# DICO_giangrandi_flipped_v100.net
KiCad netlist of a schematic drawn in EAGLE
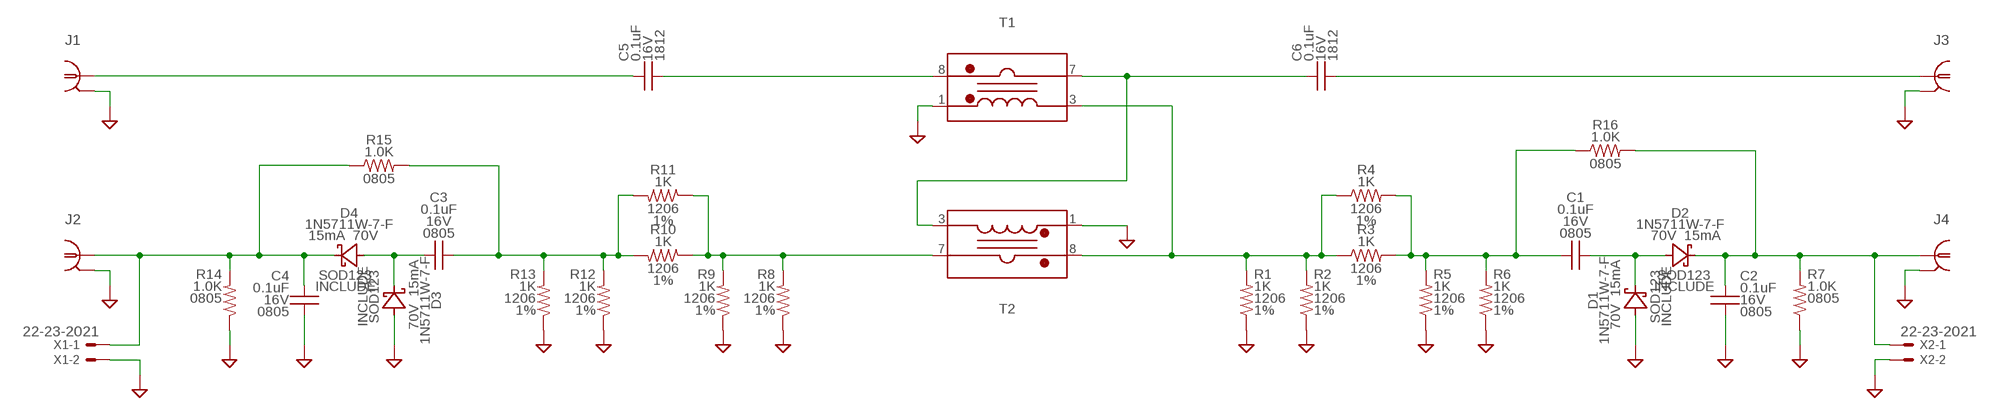
[diagram p0: schematic, sheet 1]

(export (version "E")
  (design (tool "Eeschema 10.0.6"))
  (components
    (comp (ref "C1")
      (value "0.1uF")
      (footprint "eagle-import:0805_IPC-7351B")
      (fields (field (name "PACKAGE") "0805") (field (name "VOLTAGE") "16V"))
      (libsource (lib "eagle-import") (part "C0805_IPCC-0.1U-16V-0805-X7R"))
    )
    (comp (ref "C2")
      (value "0.1uF")
      (footprint "eagle-import:0805_IPC-7351B")
      (fields (field (name "VOLTAGE") "16V"))
      (libsource (lib "eagle-import") (part "C0805_IPCC-0.1U-16V-0805-X7R"))
    )
    (comp (ref "C3")
      (value "0.1uF")
      (footprint "eagle-import:0805_IPC-7351B")
      (fields (field (name "PACKAGE") "0805") (field (name "VOLTAGE") "16V"))
      (libsource (lib "eagle-import") (part "C0805_IPCC-0.1U-16V-0805-X7R"))
    )
    (comp (ref "C4")
      (value "0.1uF")
      (footprint "eagle-import:0805_IPC-7351B")
      (fields (field (name "VOLTAGE") "16V"))
      (libsource (lib "eagle-import") (part "C0805_IPCC-0.1U-16V-0805-X7R"))
    )
    (comp (ref "C5")
      (value "0.1uF")
      (footprint "eagle-import:C1812")
      (fields (field (name "VOLTAGE") "16V"))
      (libsource (lib "eagle-import") (part "CC1812"))
    )
    (comp (ref "C6")
      (value "0.1uF")
      (footprint "eagle-import:C1812")
      (fields (field (name "VOLTAGE") "16V"))
      (libsource (lib "eagle-import") (part "CC1812"))
    )
    (comp (ref "D1")
      (value "D-SCHOTTKY1N5711W-7-FSOD123")
      (footprint "eagle-import:SOD123")
      (fields (field (name "PARTNO") "1N5711W-7-F") (field (name "VOLTAGE") "70V"))
      (libsource (lib "eagle-import") (part "D-SCHOTTKYSOD1231N5711W-7-F"))
    )
    (comp (ref "D2")
      (value "D-SCHOTTKY1N5711W-7-FSOD123")
      (footprint "eagle-import:SOD123")
      (fields (field (name "PARTNO") "1N5711W-7-F") (field (name "VOLTAGE") "70V"))
      (libsource (lib "eagle-import") (part "D-SCHOTTKYSOD1231N5711W-7-F"))
    )
    (comp (ref "D3")
      (value "D-SCHOTTKY1N5711W-7-FSOD123")
      (footprint "eagle-import:SOD123")
      (fields (field (name "PARTNO") "1N5711W-7-F") (field (name "VOLTAGE") "70V"))
      (libsource (lib "eagle-import") (part "D-SCHOTTKYSOD1231N5711W-7-F"))
    )
    (comp (ref "D4")
      (value "D-SCHOTTKY1N5711W-7-FSOD123")
      (footprint "eagle-import:SOD123")
      (fields (field (name "PARTNO") "1N5711W-7-F") (field (name "VOLTAGE") "70V"))
      (libsource (lib "eagle-import") (part "D-SCHOTTKYSOD1231N5711W-7-F"))
    )
    (comp (ref "J1")
      (value "COAXSMA_0.375WIDE")
      (footprint "eagle-import:SMA_EDGE_0.375WIDE")
      (libsource (lib "eagle-import") (part "COAXSMA_0.375WIDE"))
    )
    (comp (ref "J2")
      (value "COAXSMA_0.375WIDE")
      (footprint "eagle-import:SMA_EDGE_0.375WIDE")
      (libsource (lib "eagle-import") (part "COAXSMA_0.375WIDE"))
    )
    (comp (ref "J3")
      (value "COAXSMA_0.375WIDE")
      (footprint "eagle-import:SMA_EDGE_0.375WIDE")
      (libsource (lib "eagle-import") (part "COAXSMA_0.375WIDE"))
    )
    (comp (ref "J4")
      (value "COAXSMA_0.375WIDE")
      (footprint "eagle-import:SMA_EDGE_0.375WIDE")
      (libsource (lib "eagle-import") (part "COAXSMA_0.375WIDE"))
    )
    (comp (ref "R1")
      (value "1K")
      (footprint "eagle-import:1206_IPC-7351B")
      (fields (field (name "POWER") "0.25"))
      (libsource (lib "eagle-import") (part "R1206_IPCR-1.0K-1%-1206-0.25W"))
    )
    (comp (ref "R2")
      (value "1K")
      (footprint "eagle-import:1206_IPC-7351B")
      (fields (field (name "POWER") "0.25"))
      (libsource (lib "eagle-import") (part "R1206_IPCR-1.0K-1%-1206-0.25W"))
    )
    (comp (ref "R3")
      (value "1K")
      (footprint "eagle-import:1206_IPC-7351B")
      (fields (field (name "POWER") "0.25"))
      (libsource (lib "eagle-import") (part "R901206_IPCR-1.0K-1%-1206-0.25W"))
    )
    (comp (ref "R4")
      (value "1K")
      (footprint "eagle-import:1206_IPC-7351B")
      (fields (field (name "POWER") "0.25"))
      (libsource (lib "eagle-import") (part "R901206_IPCR-1.0K-1%-1206-0.25W"))
    )
    (comp (ref "R5")
      (value "1K")
      (footprint "eagle-import:1206_IPC-7351B")
      (fields (field (name "POWER") "0.25"))
      (libsource (lib "eagle-import") (part "R1206_IPCR-1.0K-1%-1206-0.25W"))
    )
    (comp (ref "R6")
      (value "1K")
      (footprint "eagle-import:1206_IPC-7351B")
      (fields (field (name "POWER") "0.25"))
      (libsource (lib "eagle-import") (part "R1206_IPCR-1.0K-1%-1206-0.25W"))
    )
    (comp (ref "R7")
      (value "1.0K")
      (footprint "eagle-import:0805_IPC-7351B")
      (libsource (lib "eagle-import") (part "R0805_IPCR-1.0K-0.1%-0805-0.1W"))
    )
    (comp (ref "R8")
      (value "1K")
      (footprint "eagle-import:1206_IPC-7351B")
      (fields (field (name "POWER") "0.25"))
      (libsource (lib "eagle-import") (part "R1206_IPCR-1.0K-1%-1206-0.25W"))
    )
    (comp (ref "R9")
      (value "1K")
      (footprint "eagle-import:1206_IPC-7351B")
      (fields (field (name "POWER") "0.25"))
      (libsource (lib "eagle-import") (part "R1206_IPCR-1.0K-1%-1206-0.25W"))
    )
    (comp (ref "R10")
      (value "1K")
      (footprint "eagle-import:1206_IPC-7351B")
      (fields (field (name "POWER") "0.25"))
      (libsource (lib "eagle-import") (part "R901206_IPCR-1.0K-1%-1206-0.25W"))
    )
    (comp (ref "R11")
      (value "1K")
      (footprint "eagle-import:1206_IPC-7351B")
      (fields (field (name "POWER") "0.25"))
      (libsource (lib "eagle-import") (part "R901206_IPCR-1.0K-1%-1206-0.25W"))
    )
    (comp (ref "R12")
      (value "1K")
      (footprint "eagle-import:1206_IPC-7351B")
      (fields (field (name "POWER") "0.25"))
      (libsource (lib "eagle-import") (part "R1206_IPCR-1.0K-1%-1206-0.25W"))
    )
    (comp (ref "R13")
      (value "1K")
      (footprint "eagle-import:1206_IPC-7351B")
      (fields (field (name "POWER") "0.25"))
      (libsource (lib "eagle-import") (part "R1206_IPCR-1.0K-1%-1206-0.25W"))
    )
    (comp (ref "R14")
      (value "1.0K")
      (footprint "eagle-import:0805_IPC-7351B")
      (libsource (lib "eagle-import") (part "R0805_IPCR-1.0K-0.1%-0805-0.1W"))
    )
    (comp (ref "R15")
      (value "1.0K")
      (footprint "eagle-import:0805_IPC-7351B")
      (libsource (lib "eagle-import") (part "R900805_IPCR-1.0K-0.1%-0805-0.1W"))
    )
    (comp (ref "R16")
      (value "1.0K")
      (footprint "eagle-import:0805_IPC-7351B")
      (libsource (lib "eagle-import") (part "R900805_IPCR-1.0K-0.1%-0805-0.1W"))
    )
    (comp (ref "T1")
      (value "TRAFO_CURRENTSENSEPA1005_NOCENTERPADS")
      (footprint "eagle-import:PA1005_NOCENTERPADS")
      (libsource (lib "eagle-import") (part "TRAFO_CURRENTSENSEPA1005_NOCENTERPADS"))
    )
    (comp (ref "T2")
      (value "TRAFO_CURRENTSENSEPA1005_NOCENTERPADS")
      (footprint "eagle-import:PA1005_NOCENTERPADS")
      (libsource (lib "eagle-import") (part "TRAFO_CURRENTSENSEPA1005_NOCENTERPADS"))
    )
    (comp (ref "X1")
      (value "22-23-2021")
      (footprint "eagle-import:22-23-2021")
      (fields (field (name "MF") "MOLEX"))
      (libsource (lib "eagle-import") (part "22-23-2021"))
    )
    (comp (ref "X2")
      (value "22-23-2021")
      (footprint "eagle-import:22-23-2021")
      (fields (field (name "MF") "MOLEX"))
      (libsource (lib "eagle-import") (part "22-23-2021"))
    )
  )
  (nets
    (net (code "1") (name "GND") (class "Default")
      (node (ref "C2") (pin "2") (pinfunction "2_2") (pintype "passive"))
      (node (ref "C4") (pin "2") (pinfunction "2_2") (pintype "passive"))
      (node (ref "D1") (pin "A") (pinfunction "A1_A") (pintype "passive"))
      (node (ref "D3") (pin "A") (pinfunction "A1_A") (pintype "passive"))
      (node (ref "J1") (pin "S1") (pinfunction "GND1_S1") (pintype "power_in"))
      (node (ref "J1") (pin "S2") (pinfunction "GND1_S2") (pintype "power_in"))
      (node (ref "J1") (pin "S3") (pinfunction "GND1_S3") (pintype "power_in"))
      (node (ref "J1") (pin "S4") (pinfunction "GND1_S4") (pintype "power_in"))
      (node (ref "J2") (pin "S1") (pinfunction "GND1_S1") (pintype "power_in"))
      (node (ref "J2") (pin "S2") (pinfunction "GND1_S2") (pintype "power_in"))
      (node (ref "J2") (pin "S3") (pinfunction "GND1_S3") (pintype "power_in"))
      (node (ref "J2") (pin "S4") (pinfunction "GND1_S4") (pintype "power_in"))
      (node (ref "J3") (pin "S1") (pinfunction "GND1_S1") (pintype "power_in"))
      (node (ref "J3") (pin "S2") (pinfunction "GND1_S2") (pintype "power_in"))
      (node (ref "J3") (pin "S3") (pinfunction "GND1_S3") (pintype "power_in"))
      (node (ref "J3") (pin "S4") (pinfunction "GND1_S4") (pintype "power_in"))
      (node (ref "J4") (pin "S1") (pinfunction "GND1_S1") (pintype "power_in"))
      (node (ref "J4") (pin "S2") (pinfunction "GND1_S2") (pintype "power_in"))
      (node (ref "J4") (pin "S3") (pinfunction "GND1_S3") (pintype "power_in"))
      (node (ref "J4") (pin "S4") (pinfunction "GND1_S4") (pintype "power_in"))
      (node (ref "R1") (pin "2") (pinfunction "2_2") (pintype "passive"))
      (node (ref "R12") (pin "2") (pinfunction "2_2") (pintype "passive"))
      (node (ref "R13") (pin "2") (pinfunction "2_2") (pintype "passive"))
      (node (ref "R14") (pin "2") (pinfunction "2_2") (pintype "passive"))
      (node (ref "R2") (pin "2") (pinfunction "2_2") (pintype "passive"))
      (node (ref "R5") (pin "2") (pinfunction "2_2") (pintype "passive"))
      (node (ref "R6") (pin "2") (pinfunction "2_2") (pintype "passive"))
      (node (ref "R7") (pin "2") (pinfunction "2_2") (pintype "passive"))
      (node (ref "R8") (pin "2") (pinfunction "2_2") (pintype "passive"))
      (node (ref "R9") (pin "2") (pinfunction "2_2") (pintype "passive"))
      (node (ref "T1") (pin "1") (pinfunction "SS_1") (pintype "passive"))
      (node (ref "T2") (pin "1") (pinfunction "SS_1") (pintype "passive"))
      (node (ref "X1") (pin "2") (pinfunction "S_2") (pintype "passive"))
      (node (ref "X2") (pin "2") (pinfunction "S_2") (pintype "passive"))
    )
    (net (code "2") (name "Net-(C1-Pad1)") (class "Default")
      (node (ref "C1") (pin "1") (pinfunction "1_1") (pintype "passive"))
      (node (ref "R16") (pin "1") (pinfunction "1_1") (pintype "passive"))
      (node (ref "R3") (pin "2") (pinfunction "2_2") (pintype "passive"))
      (node (ref "R4") (pin "2") (pinfunction "2_2") (pintype "passive"))
      (node (ref "R5") (pin "1") (pinfunction "1_1") (pintype "passive"))
      (node (ref "R6") (pin "1") (pinfunction "1_1") (pintype "passive"))
    )
    (net (code "3") (name "Net-(C3-Pad1)") (class "Default")
      (node (ref "C3") (pin "1") (pinfunction "1_1") (pintype "passive"))
      (node (ref "R10") (pin "2") (pinfunction "2_2") (pintype "passive"))
      (node (ref "R11") (pin "2") (pinfunction "2_2") (pintype "passive"))
      (node (ref "R12") (pin "1") (pinfunction "1_1") (pintype "passive"))
      (node (ref "R13") (pin "1") (pinfunction "1_1") (pintype "passive"))
      (node (ref "R15") (pin "2") (pinfunction "2_2") (pintype "passive"))
    )
    (net (code "4") (name "Net-(D1-C1)") (class "Default")
      (node (ref "C1") (pin "2") (pinfunction "2_2") (pintype "passive"))
      (node (ref "D1") (pin "K") (pinfunction "C1_K") (pintype "passive"))
      (node (ref "D2") (pin "A") (pinfunction "A1_A") (pintype "passive"))
    )
    (net (code "5") (name "Net-(D2-C1)") (class "Default")
      (node (ref "C2") (pin "1") (pinfunction "1_1") (pintype "passive"))
      (node (ref "D2") (pin "K") (pinfunction "C1_K") (pintype "passive"))
      (node (ref "J4") (pin "C") (pinfunction "1_C") (pintype "passive"))
      (node (ref "R16") (pin "2") (pinfunction "2_2") (pintype "passive"))
      (node (ref "R7") (pin "1") (pinfunction "1_1") (pintype "passive"))
      (node (ref "X2") (pin "1") (pinfunction "S_1") (pintype "passive"))
    )
    (net (code "6") (name "Net-(D3-C1)") (class "Default")
      (node (ref "C3") (pin "2") (pinfunction "2_2") (pintype "passive"))
      (node (ref "D3") (pin "K") (pinfunction "C1_K") (pintype "passive"))
      (node (ref "D4") (pin "A") (pinfunction "A1_A") (pintype "passive"))
    )
    (net (code "7") (name "Net-(D4-C1)") (class "Default")
      (node (ref "C4") (pin "1") (pinfunction "1_1") (pintype "passive"))
      (node (ref "D4") (pin "K") (pinfunction "C1_K") (pintype "passive"))
      (node (ref "J2") (pin "C") (pinfunction "1_C") (pintype "passive"))
      (node (ref "R14") (pin "1") (pinfunction "1_1") (pintype "passive"))
      (node (ref "R15") (pin "1") (pinfunction "1_1") (pintype "passive"))
      (node (ref "X1") (pin "1") (pinfunction "S_1") (pintype "passive"))
    )
    (net (code "8") (name "Net-(J1-1)") (class "Default")
      (node (ref "C5") (pin "1") (pinfunction "1_1") (pintype "passive"))
      (node (ref "J1") (pin "C") (pinfunction "1_C") (pintype "passive"))
    )
    (net (code "9") (name "Net-(J3-1)") (class "Default")
      (node (ref "C6") (pin "2") (pinfunction "2_2") (pintype "passive"))
      (node (ref "J3") (pin "C") (pinfunction "1_C") (pintype "passive"))
    )
    (net (code "10") (name "Net-(T1-PF)") (class "Default")
      (node (ref "C6") (pin "1") (pinfunction "1_1") (pintype "passive"))
      (node (ref "T1") (pin "7") (pinfunction "PF_7") (pintype "passive"))
      (node (ref "T2") (pin "3") (pinfunction "SF_3") (pintype "passive"))
    )
    (net (code "11") (name "Net-(T1-PS)") (class "Default")
      (node (ref "C5") (pin "2") (pinfunction "2_2") (pintype "passive"))
      (node (ref "T1") (pin "8") (pinfunction "PS_8") (pintype "passive"))
    )
    (net (code "12") (name "Net-(T1-SF)") (class "Default")
      (node (ref "R1") (pin "1") (pinfunction "1_1") (pintype "passive"))
      (node (ref "R2") (pin "1") (pinfunction "1_1") (pintype "passive"))
      (node (ref "R3") (pin "1") (pinfunction "1_1") (pintype "passive"))
      (node (ref "R4") (pin "1") (pinfunction "1_1") (pintype "passive"))
      (node (ref "T1") (pin "3") (pinfunction "SF_3") (pintype "passive"))
      (node (ref "T2") (pin "8") (pinfunction "PS_8") (pintype "passive"))
    )
    (net (code "13") (name "Net-(T2-PF)") (class "Default")
      (node (ref "R10") (pin "1") (pinfunction "1_1") (pintype "passive"))
      (node (ref "R11") (pin "1") (pinfunction "1_1") (pintype "passive"))
      (node (ref "R8") (pin "1") (pinfunction "1_1") (pintype "passive"))
      (node (ref "R9") (pin "1") (pinfunction "1_1") (pintype "passive"))
      (node (ref "T2") (pin "7") (pinfunction "PF_7") (pintype "passive"))
    )
  )
)
